# nusense-controller.net
KiCad netlist of a schematic drawn in Altium Designer
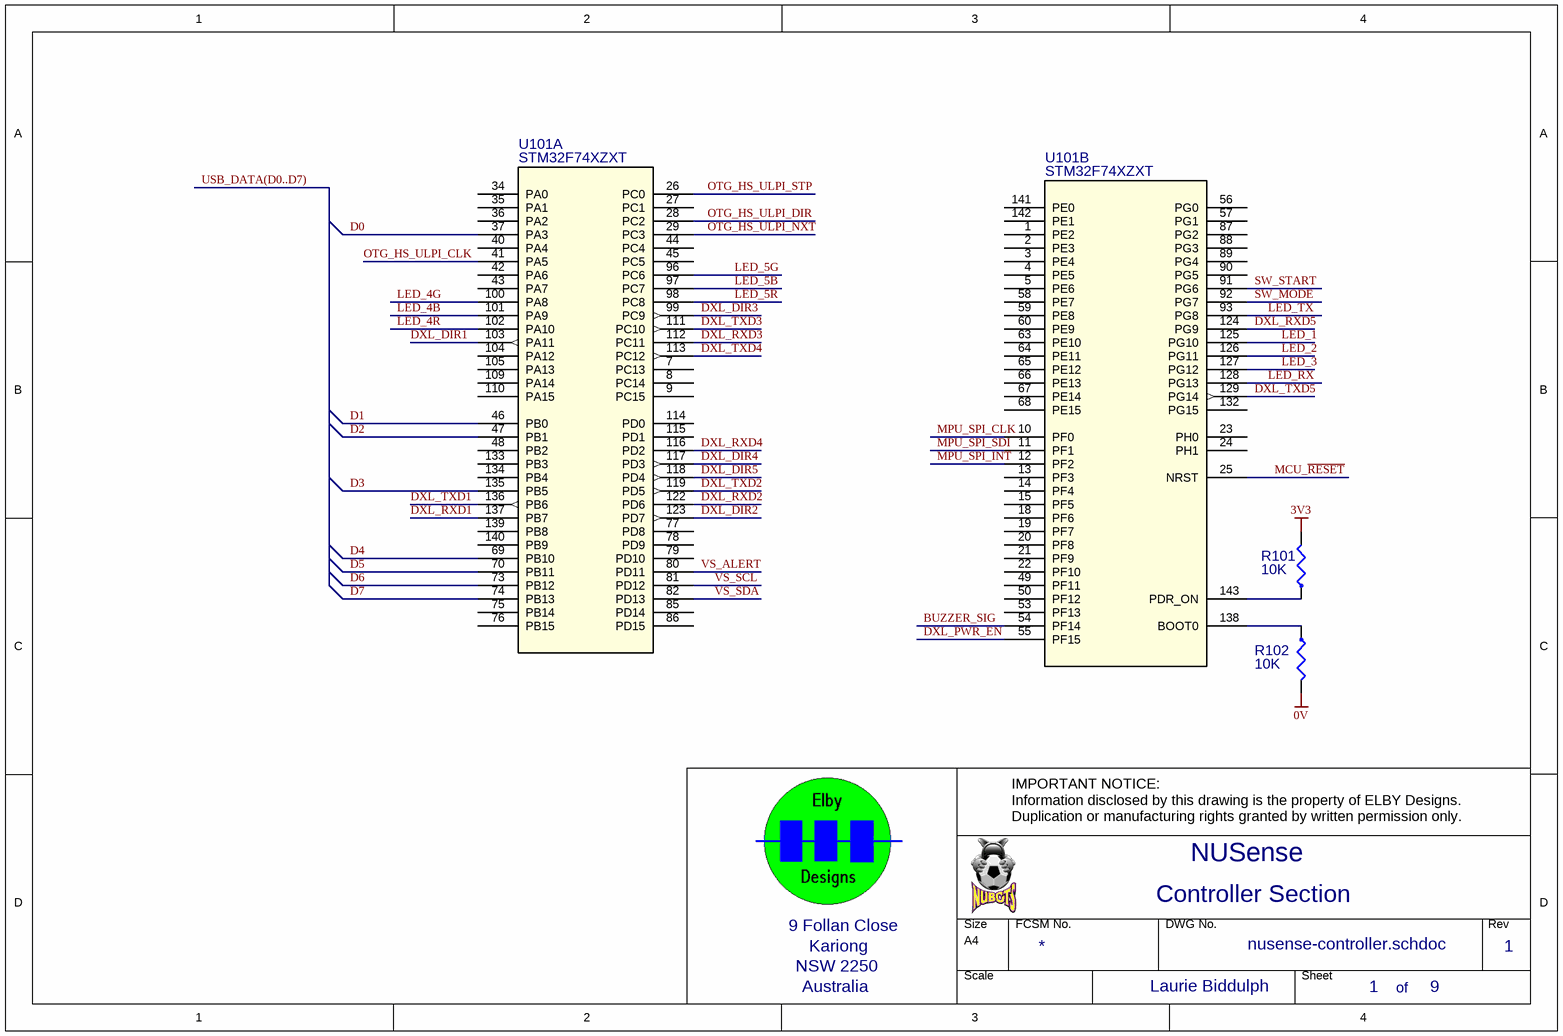
[diagram p0: nusense-controller.schdoc]

(export (version "E")
  (design (tool "Eeschema 10.0.6"))
  (components
    (comp (ref "R101")
      (value "10K")
      (footprint "AXIAL-0.4(LB)")
      (description "0.5W 1% Metal Film Resistor")
      (libsource (lib "resistor") (part "RM-10K(LB)"))
    )
    (comp (ref "R102")
      (value "10K")
      (footprint "AXIAL-0.4(LB)")
      (description "0.5W 1% Metal Film Resistor")
      (libsource (lib "resistor") (part "RM-10K(LB)"))
    )
    (comp (ref "U101")
      (value "STM32F74XZXT")
      (footprint "LQFP-144_20X20mm")
      (description "32-bit Microcontroller")
      (fields
        (field (name "MANUFACTURER_PART_NUMBER") "stm32f74xzxt")
        (field (name "COPYRIGHT") "Copyright (C) 2016 Accelerated Designs. All rights reserved")
      )
      (libsource (lib "NuBots") (part "STM32F74XZXT"))
    )
  )
  (nets
    (net (code "2") (name "/BUZZER_SIG") (class "Default")
      (node (ref "U101") (pin "54") (pinfunction "PF14_54") (pintype "passive"))
    )
    (net (code "3") (name "/D0") (class "Default")
      (node (ref "U101") (pin "37") (pinfunction "PA3_37") (pintype "passive"))
    )
    (net (code "4") (name "/D1") (class "Default")
      (node (ref "U101") (pin "46") (pinfunction "PB0_46") (pintype "passive"))
    )
    (net (code "5") (name "/D2") (class "Default")
      (node (ref "U101") (pin "47") (pinfunction "PB1_47") (pintype "passive"))
    )
    (net (code "6") (name "/D3") (class "Default")
      (node (ref "U101") (pin "135") (pinfunction "PB5_135") (pintype "passive"))
    )
    (net (code "7") (name "/D4") (class "Default")
      (node (ref "U101") (pin "69") (pinfunction "PB10_69") (pintype "passive"))
    )
    (net (code "8") (name "/D5") (class "Default")
      (node (ref "U101") (pin "70") (pinfunction "PB11_70") (pintype "passive"))
    )
    (net (code "9") (name "/D6") (class "Default")
      (node (ref "U101") (pin "73") (pinfunction "PB12_73") (pintype "passive"))
    )
    (net (code "10") (name "/D7") (class "Default")
      (node (ref "U101") (pin "74") (pinfunction "PB13_74") (pintype "passive"))
    )
    (net (code "11") (name "/DXL_DIR1") (class "Default")
      (node (ref "U101") (pin "103") (pinfunction "PA11_103") (pintype "output"))
    )
    (net (code "12") (name "/DXL_DIR2") (class "Default")
      (node (ref "U101") (pin "123") (pinfunction "PD7_123") (pintype "output"))
    )
    (net (code "13") (name "/DXL_DIR3") (class "Default")
      (node (ref "U101") (pin "99") (pinfunction "PC9_99") (pintype "output"))
    )
    (net (code "14") (name "/DXL_DIR4") (class "Default")
      (node (ref "U101") (pin "117") (pinfunction "PD3_117") (pintype "output"))
    )
    (net (code "15") (name "/DXL_DIR5") (class "Default")
      (node (ref "U101") (pin "118") (pinfunction "PD4_118") (pintype "output"))
    )
    (net (code "16") (name "/DXL_PWR_EN") (class "Default")
      (node (ref "U101") (pin "55") (pinfunction "PF15_55") (pintype "passive"))
    )
    (net (code "17") (name "/DXL_RXD1") (class "Default")
      (node (ref "U101") (pin "137") (pinfunction "PB7_137") (pintype "passive"))
    )
    (net (code "18") (name "/DXL_RXD2") (class "Default")
      (node (ref "U101") (pin "122") (pinfunction "PD6_122") (pintype "passive"))
    )
    (net (code "19") (name "/DXL_RXD3") (class "Default")
      (node (ref "U101") (pin "112") (pinfunction "PC11_112") (pintype "passive"))
    )
    (net (code "20") (name "/DXL_RXD4") (class "Default")
      (node (ref "U101") (pin "116") (pinfunction "PD2_116") (pintype "passive"))
    )
    (net (code "21") (name "/DXL_RXD5") (class "Default")
      (node (ref "U101") (pin "124") (pinfunction "PG9_124") (pintype "passive"))
    )
    (net (code "22") (name "/DXL_TXD1") (class "Default")
      (node (ref "U101") (pin "136") (pinfunction "PB6_136") (pintype "output"))
    )
    (net (code "23") (name "/DXL_TXD2") (class "Default")
      (node (ref "U101") (pin "119") (pinfunction "PD5_119") (pintype "output"))
    )
    (net (code "24") (name "/DXL_TXD3") (class "Default")
      (node (ref "U101") (pin "111") (pinfunction "PC10_111") (pintype "output"))
    )
    (net (code "25") (name "/DXL_TXD4") (class "Default")
      (node (ref "U101") (pin "113") (pinfunction "PC12_113") (pintype "output"))
    )
    (net (code "26") (name "/DXL_TXD5") (class "Default")
      (node (ref "U101") (pin "129") (pinfunction "PG14_129") (pintype "passive"))
    )
    (net (code "27") (name "/LED_1") (class "Default")
      (node (ref "U101") (pin "125") (pinfunction "PG10_125") (pintype "passive"))
    )
    (net (code "28") (name "/LED_2") (class "Default")
      (node (ref "U101") (pin "126") (pinfunction "PG11_126") (pintype "passive"))
    )
    (net (code "29") (name "/LED_3") (class "Default")
      (node (ref "U101") (pin "127") (pinfunction "PG12_127") (pintype "passive"))
    )
    (net (code "30") (name "/LED_4B") (class "Default")
      (node (ref "U101") (pin "101") (pinfunction "PA9_101") (pintype "passive"))
    )
    (net (code "31") (name "/LED_4G") (class "Default")
      (node (ref "U101") (pin "100") (pinfunction "PA8_100") (pintype "passive"))
    )
    (net (code "32") (name "/LED_4R") (class "Default")
      (node (ref "U101") (pin "102") (pinfunction "PA10_102") (pintype "passive"))
    )
    (net (code "33") (name "/LED_5B") (class "Default")
      (node (ref "U101") (pin "97") (pinfunction "PC7_97") (pintype "passive"))
    )
    (net (code "34") (name "/LED_5G") (class "Default")
      (node (ref "U101") (pin "96") (pinfunction "PC6_96") (pintype "passive"))
    )
    (net (code "35") (name "/LED_5R") (class "Default")
      (node (ref "U101") (pin "98") (pinfunction "PC8_98") (pintype "passive"))
    )
    (net (code "36") (name "/LED_RX") (class "Default")
      (node (ref "U101") (pin "128") (pinfunction "PG13_128") (pintype "passive"))
    )
    (net (code "37") (name "/LED_TX") (class "Default")
      (node (ref "U101") (pin "93") (pinfunction "PG8_93") (pintype "passive"))
    )
    (net (code "38") (name "/MCU_~{RESET}") (class "Default")
      (node (ref "U101") (pin "25") (pinfunction "NRST_25") (pintype "passive"))
    )
    (net (code "39") (name "/MPU_SPI_CLK") (class "Default")
      (node (ref "U101") (pin "10") (pinfunction "PF0_10") (pintype "passive"))
    )
    (net (code "40") (name "/MPU_SPI_INT") (class "Default")
      (node (ref "U101") (pin "12") (pinfunction "PF2_12") (pintype "passive"))
    )
    (net (code "41") (name "/MPU_SPI_SDI") (class "Default")
      (node (ref "U101") (pin "11") (pinfunction "PF1_11") (pintype "passive"))
    )
    (net (code "42") (name "/OTG_HS_ULPI_CLK") (class "Default")
      (node (ref "U101") (pin "41") (pinfunction "PA5_41") (pintype "passive"))
    )
    (net (code "43") (name "/OTG_HS_ULPI_DIR") (class "Default")
      (node (ref "U101") (pin "28") (pinfunction "PC2_28") (pintype "passive"))
    )
    (net (code "44") (name "/OTG_HS_ULPI_NXT") (class "Default")
      (node (ref "U101") (pin "29") (pinfunction "PC3_29") (pintype "passive"))
    )
    (net (code "45") (name "/OTG_HS_ULPI_STP") (class "Default")
      (node (ref "U101") (pin "26") (pinfunction "PC0_26") (pintype "passive"))
    )
    (net (code "46") (name "/SW_MODE") (class "Default")
      (node (ref "U101") (pin "92") (pinfunction "PG7_92") (pintype "passive"))
    )
    (net (code "47") (name "/SW_START") (class "Default")
      (node (ref "U101") (pin "91") (pinfunction "PG6_91") (pintype "passive"))
    )
    (net (code "48") (name "/VS_ALERT") (class "Default")
      (node (ref "U101") (pin "80") (pinfunction "PD11_80") (pintype "passive"))
    )
    (net (code "49") (name "/VS_SCL") (class "Default")
      (node (ref "U101") (pin "81") (pinfunction "PD12_81") (pintype "passive"))
    )
    (net (code "50") (name "/VS_SDA") (class "Default")
      (node (ref "U101") (pin "82") (pinfunction "PD13_82") (pintype "passive"))
    )
    (net (code "52") (name "0V") (class "Default")
      (node (ref "R102") (pin "2") (pinfunction "2_2") (pintype "passive"))
    )
    (net (code "53") (name "3V3") (class "Default")
      (node (ref "R101") (pin "2") (pinfunction "2_2") (pintype "passive"))
    )
    (net (code "54") (name "Net-(U101B-BOOT0)") (class "Default")
      (node (ref "R102") (pin "1") (pinfunction "1_1") (pintype "passive"))
      (node (ref "U101") (pin "138") (pinfunction "BOOT0_138") (pintype "input"))
    )
    (net (code "55") (name "Net-(U101B-PDR_ON)") (class "Default")
      (node (ref "R101") (pin "1") (pinfunction "1_1") (pintype "passive"))
      (node (ref "U101") (pin "143") (pinfunction "PDR_ON_143") (pintype "passive"))
    )
    (net (code "56") (name "unconnected-(U101A-PA0-Pad34)") (class "Default")
      (node (ref "U101") (pin "34") (pinfunction "PA0_34") (pintype "passive"))
    )
    (net (code "57") (name "unconnected-(U101A-PA1-Pad35)") (class "Default")
      (node (ref "U101") (pin "35") (pinfunction "PA1_35") (pintype "passive"))
    )
    (net (code "58") (name "unconnected-(U101A-PA2-Pad36)") (class "Default")
      (node (ref "U101") (pin "36") (pinfunction "PA2_36") (pintype "passive"))
    )
    (net (code "59") (name "unconnected-(U101A-PA4-Pad40)") (class "Default")
      (node (ref "U101") (pin "40") (pinfunction "PA4_40") (pintype "passive"))
    )
    (net (code "60") (name "unconnected-(U101A-PA6-Pad42)") (class "Default")
      (node (ref "U101") (pin "42") (pinfunction "PA6_42") (pintype "passive"))
    )
    (net (code "61") (name "unconnected-(U101A-PA7-Pad43)") (class "Default")
      (node (ref "U101") (pin "43") (pinfunction "PA7_43") (pintype "passive"))
    )
    (net (code "62") (name "unconnected-(U101A-PA12-Pad104)") (class "Default")
      (node (ref "U101") (pin "104") (pinfunction "PA12_104") (pintype "passive"))
    )
    (net (code "63") (name "unconnected-(U101A-PA13-Pad105)") (class "Default")
      (node (ref "U101") (pin "105") (pinfunction "PA13_105") (pintype "passive"))
    )
    (net (code "64") (name "unconnected-(U101A-PA14-Pad109)") (class "Default")
      (node (ref "U101") (pin "109") (pinfunction "PA14_109") (pintype "passive"))
    )
    (net (code "65") (name "unconnected-(U101A-PA15-Pad110)") (class "Default")
      (node (ref "U101") (pin "110") (pinfunction "PA15_110") (pintype "passive"))
    )
    (net (code "66") (name "unconnected-(U101A-PB2-Pad48)") (class "Default")
      (node (ref "U101") (pin "48") (pinfunction "PB2_48") (pintype "passive"))
    )
    (net (code "67") (name "unconnected-(U101A-PB3-Pad133)") (class "Default")
      (node (ref "U101") (pin "133") (pinfunction "PB3_133") (pintype "passive"))
    )
    (net (code "68") (name "unconnected-(U101A-PB4-Pad134)") (class "Default")
      (node (ref "U101") (pin "134") (pinfunction "PB4_134") (pintype "passive"))
    )
    (net (code "69") (name "unconnected-(U101A-PB8-Pad139)") (class "Default")
      (node (ref "U101") (pin "139") (pinfunction "PB8_139") (pintype "passive"))
    )
    (net (code "70") (name "unconnected-(U101A-PB9-Pad140)") (class "Default")
      (node (ref "U101") (pin "140") (pinfunction "PB9_140") (pintype "passive"))
    )
    (net (code "71") (name "unconnected-(U101A-PB14-Pad75)") (class "Default")
      (node (ref "U101") (pin "75") (pinfunction "PB14_75") (pintype "passive"))
    )
    (net (code "72") (name "unconnected-(U101A-PB15-Pad76)") (class "Default")
      (node (ref "U101") (pin "76") (pinfunction "PB15_76") (pintype "passive"))
    )
    (net (code "73") (name "unconnected-(U101A-PC1-Pad27)") (class "Default")
      (node (ref "U101") (pin "27") (pinfunction "PC1_27") (pintype "passive"))
    )
    (net (code "74") (name "unconnected-(U101A-PC4-Pad44)") (class "Default")
      (node (ref "U101") (pin "44") (pinfunction "PC4_44") (pintype "passive"))
    )
    (net (code "75") (name "unconnected-(U101A-PC5-Pad45)") (class "Default")
      (node (ref "U101") (pin "45") (pinfunction "PC5_45") (pintype "passive"))
    )
    (net (code "76") (name "unconnected-(U101A-PC13-Pad7)") (class "Default")
      (node (ref "U101") (pin "7") (pinfunction "PC13_7") (pintype "passive"))
    )
    (net (code "77") (name "unconnected-(U101A-PC14-Pad8)") (class "Default")
      (node (ref "U101") (pin "8") (pinfunction "PC14_8") (pintype "passive"))
    )
    (net (code "78") (name "unconnected-(U101A-PC15-Pad9)") (class "Default")
      (node (ref "U101") (pin "9") (pinfunction "PC15_9") (pintype "passive"))
    )
    (net (code "79") (name "unconnected-(U101A-PD0-Pad114)") (class "Default")
      (node (ref "U101") (pin "114") (pinfunction "PD0_114") (pintype "passive"))
    )
    (net (code "80") (name "unconnected-(U101A-PD1-Pad115)") (class "Default")
      (node (ref "U101") (pin "115") (pinfunction "PD1_115") (pintype "passive"))
    )
    (net (code "81") (name "unconnected-(U101A-PD8-Pad77)") (class "Default")
      (node (ref "U101") (pin "77") (pinfunction "PD8_77") (pintype "passive"))
    )
    (net (code "82") (name "unconnected-(U101A-PD9-Pad78)") (class "Default")
      (node (ref "U101") (pin "78") (pinfunction "PD9_78") (pintype "passive"))
    )
    (net (code "83") (name "unconnected-(U101A-PD10-Pad79)") (class "Default")
      (node (ref "U101") (pin "79") (pinfunction "PD10_79") (pintype "passive"))
    )
    (net (code "84") (name "unconnected-(U101A-PD14-Pad85)") (class "Default")
      (node (ref "U101") (pin "85") (pinfunction "PD14_85") (pintype "passive"))
    )
    (net (code "85") (name "unconnected-(U101A-PD15-Pad86)") (class "Default")
      (node (ref "U101") (pin "86") (pinfunction "PD15_86") (pintype "passive"))
    )
    (net (code "86") (name "unconnected-(U101B-PE0-Pad141)") (class "Default")
      (node (ref "U101") (pin "141") (pinfunction "PE0_141") (pintype "passive"))
    )
    (net (code "87") (name "unconnected-(U101B-PE1-Pad142)") (class "Default")
      (node (ref "U101") (pin "142") (pinfunction "PE1_142") (pintype "passive"))
    )
    (net (code "88") (name "unconnected-(U101B-PE2-Pad1)") (class "Default")
      (node (ref "U101") (pin "1") (pinfunction "PE2_1") (pintype "passive"))
    )
    (net (code "89") (name "unconnected-(U101B-PE3-Pad2)") (class "Default")
      (node (ref "U101") (pin "2") (pinfunction "PE3_2") (pintype "passive"))
    )
    (net (code "90") (name "unconnected-(U101B-PE4-Pad3)") (class "Default")
      (node (ref "U101") (pin "3") (pinfunction "PE4_3") (pintype "passive"))
    )
    (net (code "91") (name "unconnected-(U101B-PE5-Pad4)") (class "Default")
      (node (ref "U101") (pin "4") (pinfunction "PE5_4") (pintype "passive"))
    )
    (net (code "92") (name "unconnected-(U101B-PE6-Pad5)") (class "Default")
      (node (ref "U101") (pin "5") (pinfunction "PE6_5") (pintype "passive"))
    )
    (net (code "93") (name "unconnected-(U101B-PE7-Pad58)") (class "Default")
      (node (ref "U101") (pin "58") (pinfunction "PE7_58") (pintype "passive"))
    )
    (net (code "94") (name "unconnected-(U101B-PE8-Pad59)") (class "Default")
      (node (ref "U101") (pin "59") (pinfunction "PE8_59") (pintype "passive"))
    )
    (net (code "95") (name "unconnected-(U101B-PE9-Pad60)") (class "Default")
      (node (ref "U101") (pin "60") (pinfunction "PE9_60") (pintype "passive"))
    )
    (net (code "96") (name "unconnected-(U101B-PE10-Pad63)") (class "Default")
      (node (ref "U101") (pin "63") (pinfunction "PE10_63") (pintype "passive"))
    )
    (net (code "97") (name "unconnected-(U101B-PE11-Pad64)") (class "Default")
      (node (ref "U101") (pin "64") (pinfunction "PE11_64") (pintype "passive"))
    )
    (net (code "98") (name "unconnected-(U101B-PE12-Pad65)") (class "Default")
      (node (ref "U101") (pin "65") (pinfunction "PE12_65") (pintype "passive"))
    )
    (net (code "99") (name "unconnected-(U101B-PE13-Pad66)") (class "Default")
      (node (ref "U101") (pin "66") (pinfunction "PE13_66") (pintype "passive"))
    )
    (net (code "100") (name "unconnected-(U101B-PE14-Pad67)") (class "Default")
      (node (ref "U101") (pin "67") (pinfunction "PE14_67") (pintype "passive"))
    )
    (net (code "101") (name "unconnected-(U101B-PE15-Pad68)") (class "Default")
      (node (ref "U101") (pin "68") (pinfunction "PE15_68") (pintype "passive"))
    )
    (net (code "102") (name "unconnected-(U101B-PF3-Pad13)") (class "Default")
      (node (ref "U101") (pin "13") (pinfunction "PF3_13") (pintype "passive"))
    )
    (net (code "103") (name "unconnected-(U101B-PF4-Pad14)") (class "Default")
      (node (ref "U101") (pin "14") (pinfunction "PF4_14") (pintype "passive"))
    )
    (net (code "104") (name "unconnected-(U101B-PF5-Pad15)") (class "Default")
      (node (ref "U101") (pin "15") (pinfunction "PF5_15") (pintype "passive"))
    )
    (net (code "105") (name "unconnected-(U101B-PF6-Pad18)") (class "Default")
      (node (ref "U101") (pin "18") (pinfunction "PF6_18") (pintype "passive"))
    )
    (net (code "106") (name "unconnected-(U101B-PF7-Pad19)") (class "Default")
      (node (ref "U101") (pin "19") (pinfunction "PF7_19") (pintype "passive"))
    )
    (net (code "107") (name "unconnected-(U101B-PF8-Pad20)") (class "Default")
      (node (ref "U101") (pin "20") (pinfunction "PF8_20") (pintype "passive"))
    )
    (net (code "108") (name "unconnected-(U101B-PF9-Pad21)") (class "Default")
      (node (ref "U101") (pin "21") (pinfunction "PF9_21") (pintype "passive"))
    )
    (net (code "109") (name "unconnected-(U101B-PF10-Pad22)") (class "Default")
      (node (ref "U101") (pin "22") (pinfunction "PF10_22") (pintype "passive"))
    )
    (net (code "110") (name "unconnected-(U101B-PF11-Pad49)") (class "Default")
      (node (ref "U101") (pin "49") (pinfunction "PF11_49") (pintype "passive"))
    )
    (net (code "111") (name "unconnected-(U101B-PF12-Pad50)") (class "Default")
      (node (ref "U101") (pin "50") (pinfunction "PF12_50") (pintype "passive"))
    )
    (net (code "112") (name "unconnected-(U101B-PF13-Pad53)") (class "Default")
      (node (ref "U101") (pin "53") (pinfunction "PF13_53") (pintype "passive"))
    )
    (net (code "113") (name "unconnected-(U101B-PG0-Pad56)") (class "Default")
      (node (ref "U101") (pin "56") (pinfunction "PG0_56") (pintype "passive"))
    )
    (net (code "114") (name "unconnected-(U101B-PG1-Pad57)") (class "Default")
      (node (ref "U101") (pin "57") (pinfunction "PG1_57") (pintype "passive"))
    )
    (net (code "115") (name "unconnected-(U101B-PG2-Pad87)") (class "Default")
      (node (ref "U101") (pin "87") (pinfunction "PG2_87") (pintype "passive"))
    )
    (net (code "116") (name "unconnected-(U101B-PG3-Pad88)") (class "Default")
      (node (ref "U101") (pin "88") (pinfunction "PG3_88") (pintype "passive"))
    )
    (net (code "117") (name "unconnected-(U101B-PG4-Pad89)") (class "Default")
      (node (ref "U101") (pin "89") (pinfunction "PG4_89") (pintype "passive"))
    )
    (net (code "118") (name "unconnected-(U101B-PG5-Pad90)") (class "Default")
      (node (ref "U101") (pin "90") (pinfunction "PG5_90") (pintype "passive"))
    )
    (net (code "119") (name "unconnected-(U101B-PG15-Pad132)") (class "Default")
      (node (ref "U101") (pin "132") (pinfunction "PG15_132") (pintype "passive"))
    )
    (net (code "120") (name "unconnected-(U101B-PH0-Pad23)") (class "Default")
      (node (ref "U101") (pin "23") (pinfunction "PH0_23") (pintype "passive"))
    )
    (net (code "121") (name "unconnected-(U101B-PH1-Pad24)") (class "Default")
      (node (ref "U101") (pin "24") (pinfunction "PH1_24") (pintype "passive"))
    )
  )
)
